# Ardumouse-LiION_rev3.net
KiCad netlist of a schematic drawn in EAGLE
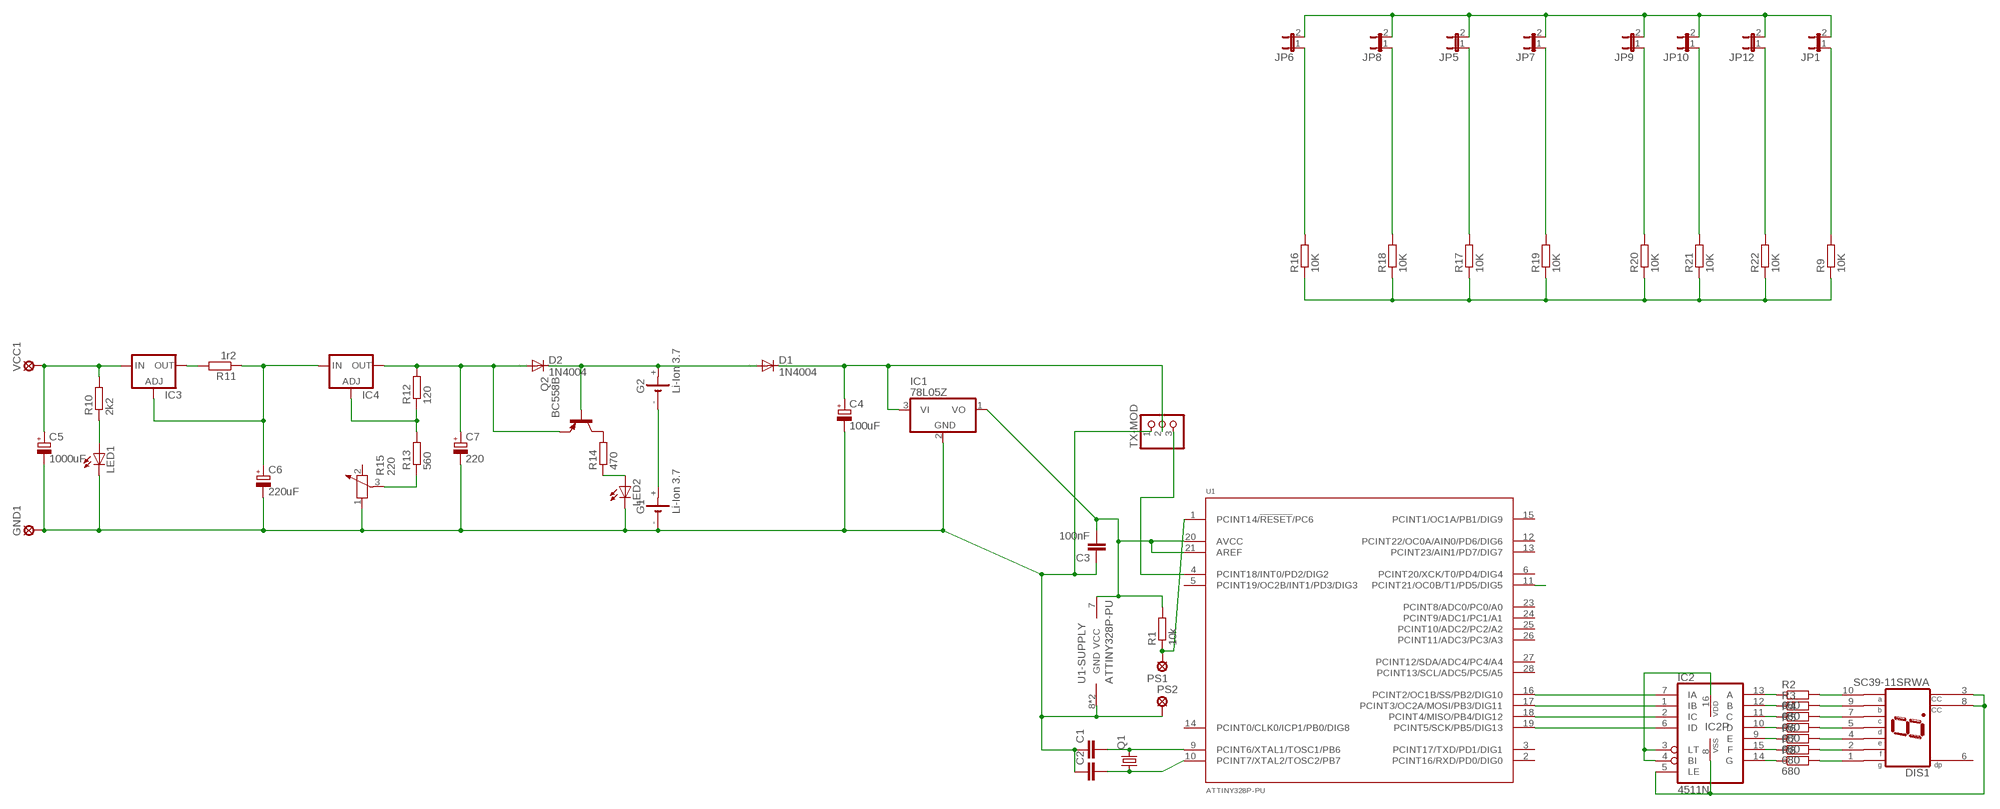
[diagram p0: schematic, sheet 1]

(export (version "E")
  (design (tool "Eeschema 10.0.6"))
  (components
    (comp (ref "C1")
      (value "C2,5-3")
      (footprint "eagle-import:C2.5-3")
      (libsource (lib "eagle-import") (part "C2,5-3"))
    )
    (comp (ref "C2")
      (value "C2,5-3")
      (footprint "eagle-import:C2.5-3")
      (libsource (lib "eagle-import") (part "C2,5-3"))
    )
    (comp (ref "C3")
      (value "100nF")
      (footprint "eagle-import:C2.5-3")
      (libsource (lib "eagle-import") (part "C2,5-3"))
    )
    (comp (ref "C4")
      (value "100uF")
      (footprint "eagle-import:E3,5-8")
      (libsource (lib "eagle-import") (part "resistor_CPOL-EUE3.5-8"))
    )
    (comp (ref "C5")
      (value "1000uF")
      (footprint "eagle-import:E3,5-8")
      (libsource (lib "eagle-import") (part "CPOL-EUE3.5-8"))
    )
    (comp (ref "C6")
      (value "220uF")
      (footprint "eagle-import:E3,5-8")
      (libsource (lib "eagle-import") (part "CPOL-EUE3.5-8"))
    )
    (comp (ref "C7")
      (value "220")
      (footprint "eagle-import:E3,5-8")
      (libsource (lib "eagle-import") (part "CPOL-EUE3.5-8"))
    )
    (comp (ref "D1")
      (value "1N4004")
      (footprint "eagle-import:DO41-10")
      (libsource (lib "eagle-import") (part "1N4004"))
    )
    (comp (ref "D2")
      (value "1N4004")
      (footprint "eagle-import:DO41-10")
      (libsource (lib "eagle-import") (part "1N4004"))
    )
    (comp (ref "DIS1")
      (value "SC39-11SRWA")
      (footprint "eagle-import:HDSP-E")
      (libsource (lib "eagle-import") (part "SC39-11SRWA"))
    )
    (comp (ref "G1")
      (value "Li-Ion 3.7")
      (footprint "eagle-import:SL-160AA_PR")
      (libsource (lib "eagle-import") (part "SL-160AA/PR"))
    )
    (comp (ref "G2")
      (value "Li-Ion 3.7")
      (footprint "eagle-import:SL-160AA_PR")
      (libsource (lib "eagle-import") (part "SL-160AA/PR"))
    )
    (comp (ref "GND1")
      (value "LSP13")
      (footprint "eagle-import:LSP13")
      (libsource (lib "eagle-import") (part "LSP13"))
    )
    (comp (ref "IC1")
      (value "78L05Z")
      (footprint "eagle-import:TO92")
      (libsource (lib "eagle-import") (part "78ZL05"))
    )
    (comp (ref "IC2")
      (value "4511N")
      (footprint "eagle-import:DIL16")
      (libsource (lib "eagle-import") (part "4511N"))
    )
    (comp (ref "IC3")
      (value "LM317TS")
      (footprint "eagle-import:317TS")
      (libsource (lib "eagle-import") (part "LM317TS"))
    )
    (comp (ref "IC4")
      (value "LM317TS")
      (footprint "eagle-import:317TS")
      (libsource (lib "eagle-import") (part "LM317TS"))
    )
    (comp (ref "JP1")
      (value "JP1E")
      (footprint "eagle-import:JP1")
      (libsource (lib "eagle-import") (part "JP1E"))
    )
    (comp (ref "JP5")
      (value "JP1E")
      (footprint "eagle-import:JP1")
      (libsource (lib "eagle-import") (part "JP1E"))
    )
    (comp (ref "JP6")
      (value "JP1E")
      (footprint "eagle-import:JP1")
      (libsource (lib "eagle-import") (part "JP1E"))
    )
    (comp (ref "JP7")
      (value "JP1E")
      (footprint "eagle-import:JP1")
      (libsource (lib "eagle-import") (part "JP1E"))
    )
    (comp (ref "JP8")
      (value "JP1E")
      (footprint "eagle-import:JP1")
      (libsource (lib "eagle-import") (part "JP1E"))
    )
    (comp (ref "JP9")
      (value "JP1E")
      (footprint "eagle-import:JP1")
      (libsource (lib "eagle-import") (part "JP1E"))
    )
    (comp (ref "JP10")
      (value "JP1E")
      (footprint "eagle-import:JP1")
      (libsource (lib "eagle-import") (part "JP1E"))
    )
    (comp (ref "JP12")
      (value "JP1E")
      (footprint "eagle-import:JP1")
      (libsource (lib "eagle-import") (part "JP1E"))
    )
    (comp (ref "LED1")
      (value "LED5MM")
      (footprint "eagle-import:LED5MM")
      (libsource (lib "eagle-import") (part "LED5MM"))
    )
    (comp (ref "LED2")
      (value "LED5MM")
      (footprint "eagle-import:LED5MM")
      (libsource (lib "eagle-import") (part "LED5MM"))
    )
    (comp (ref "PS1")
      (value "LSP10")
      (footprint "eagle-import:LSP10")
      (libsource (lib "eagle-import") (part "LSP10"))
    )
    (comp (ref "PS2")
      (value "LSP10")
      (footprint "eagle-import:LSP10")
      (libsource (lib "eagle-import") (part "LSP10"))
    )
    (comp (ref "Q1")
      (value "CRYSTALHC49S")
      (footprint "eagle-import:HC49_S")
      (libsource (lib "eagle-import") (part "CRYSTALHC49S"))
    )
    (comp (ref "Q2")
      (value "BC558B")
      (footprint "eagle-import:TO92-EBC")
      (libsource (lib "eagle-import") (part "BC558B"))
    )
    (comp (ref "R1")
      (value "10k")
      (footprint "eagle-import:0204_7")
      (libsource (lib "eagle-import") (part "resistor_R-EU_0204/7"))
    )
    (comp (ref "R2")
      (value "680")
      (footprint "eagle-import:0204_7")
      (libsource (lib "eagle-import") (part "resistor_R-EU_0204/7"))
    )
    (comp (ref "R3")
      (value "680")
      (footprint "eagle-import:0204_7")
      (libsource (lib "eagle-import") (part "resistor_R-EU_0204/7"))
    )
    (comp (ref "R4")
      (value "680")
      (footprint "eagle-import:0204_7")
      (libsource (lib "eagle-import") (part "resistor_R-EU_0204/7"))
    )
    (comp (ref "R5")
      (value "680")
      (footprint "eagle-import:0204_7")
      (libsource (lib "eagle-import") (part "resistor_R-EU_0204/7"))
    )
    (comp (ref "R6")
      (value "680")
      (footprint "eagle-import:0204_7")
      (libsource (lib "eagle-import") (part "resistor_R-EU_0204/7"))
    )
    (comp (ref "R7")
      (value "680")
      (footprint "eagle-import:0204_7")
      (libsource (lib "eagle-import") (part "resistor_R-EU_0204/7"))
    )
    (comp (ref "R8")
      (value "680")
      (footprint "eagle-import:0204_7")
      (libsource (lib "eagle-import") (part "resistor_R-EU_0204/7"))
    )
    (comp (ref "R9")
      (value "10K")
      (footprint "eagle-import:0204_7")
      (libsource (lib "eagle-import") (part "R-EU_0204/7"))
    )
    (comp (ref "R10")
      (value "2k2")
      (footprint "eagle-import:0207_7")
      (libsource (lib "eagle-import") (part "R-EU_0207/7"))
    )
    (comp (ref "R11")
      (value "1r2")
      (footprint "eagle-import:0207_7")
      (libsource (lib "eagle-import") (part "R-EU_0207/7"))
    )
    (comp (ref "R12")
      (value "120")
      (footprint "eagle-import:0207_7")
      (libsource (lib "eagle-import") (part "R-EU_0207/7"))
    )
    (comp (ref "R13")
      (value "560")
      (footprint "eagle-import:0207_7")
      (libsource (lib "eagle-import") (part "R-EU_0207/7"))
    )
    (comp (ref "R14")
      (value "470")
      (footprint "eagle-import:0207_7")
      (libsource (lib "eagle-import") (part "R-EU_0207/7"))
    )
    (comp (ref "R15")
      (value "220")
      (footprint "eagle-import:PT-10")
      (libsource (lib "eagle-import") (part "POTENTIOMETER_PT-10"))
    )
    (comp (ref "R16")
      (value "10K")
      (footprint "eagle-import:0204_7")
      (libsource (lib "eagle-import") (part "R-EU_0204/7"))
    )
    (comp (ref "R17")
      (value "10K")
      (footprint "eagle-import:0204_7")
      (libsource (lib "eagle-import") (part "R-EU_0204/7"))
    )
    (comp (ref "R18")
      (value "10K")
      (footprint "eagle-import:0204_7")
      (libsource (lib "eagle-import") (part "R-EU_0204/7"))
    )
    (comp (ref "R19")
      (value "10K")
      (footprint "eagle-import:0204_7")
      (libsource (lib "eagle-import") (part "R-EU_0204/7"))
    )
    (comp (ref "R20")
      (value "10K")
      (footprint "eagle-import:0204_7")
      (libsource (lib "eagle-import") (part "R-EU_0204/7"))
    )
    (comp (ref "R21")
      (value "10K")
      (footprint "eagle-import:0204_7")
      (libsource (lib "eagle-import") (part "R-EU_0204/7"))
    )
    (comp (ref "R22")
      (value "10K")
      (footprint "eagle-import:0204_7")
      (libsource (lib "eagle-import") (part "R-EU_0204/7"))
    )
    (comp (ref "TX-MOD")
      (value "PINHD-1X3")
      (footprint "eagle-import:1X03")
      (libsource (lib "eagle-import") (part "PINHD-1X3"))
    )
    (comp (ref "U1")
      (value "ATTINY328P-PU")
      (footprint "eagle-import:DIP-28")
      (fields (field (name "MANUFACTURER") "Atmel") (field (name "PART_NUMBER") "ATMEGA328P-PU"))
      (libsource (lib "eagle-import") (part "ATTINY8P-?PU32"))
    )
    (comp (ref "VCC1")
      (value "LSP13")
      (footprint "eagle-import:LSP13")
      (libsource (lib "eagle-import") (part "LSP13"))
    )
  )
  (nets
    (net (code "1") (name "Net-(D1-PadA)") (class "Default")
      (node (ref "D1") (pin "A") (pinfunction "A_A") (pintype "passive"))
      (node (ref "D2") (pin "C") (pinfunction "C_C") (pintype "passive"))
      (node (ref "G2") (pin "+") (pinfunction "+_+") (pintype "passive"))
      (node (ref "Q2") (pin "B") (pinfunction "B_B") (pintype "passive"))
    )
    (net (code "2") (name "Net-(DIS1-A)") (class "Default")
      (node (ref "DIS1") (pin "10") (pinfunction "A_10") (pintype "passive"))
      (node (ref "R2") (pin "2") (pinfunction "2_2") (pintype "passive"))
    )
    (net (code "3") (name "Net-(DIS1-B)") (class "Default")
      (node (ref "DIS1") (pin "9") (pinfunction "B_9") (pintype "passive"))
      (node (ref "R3") (pin "2") (pinfunction "2_2") (pintype "passive"))
    )
    (net (code "4") (name "Net-(DIS1-C)") (class "Default")
      (node (ref "DIS1") (pin "7") (pinfunction "C_7") (pintype "passive"))
      (node (ref "R4") (pin "2") (pinfunction "2_2") (pintype "passive"))
    )
    (net (code "5") (name "Net-(DIS1-D)") (class "Default")
      (node (ref "DIS1") (pin "5") (pinfunction "D_5") (pintype "passive"))
      (node (ref "R5") (pin "2") (pinfunction "2_2") (pintype "passive"))
    )
    (net (code "6") (name "Net-(DIS1-E)") (class "Default")
      (node (ref "DIS1") (pin "4") (pinfunction "E_4") (pintype "passive"))
      (node (ref "R6") (pin "2") (pinfunction "2_2") (pintype "passive"))
    )
    (net (code "7") (name "Net-(DIS1-F)") (class "Default")
      (node (ref "DIS1") (pin "2") (pinfunction "F_2") (pintype "passive"))
      (node (ref "R7") (pin "2") (pinfunction "2_2") (pintype "passive"))
    )
    (net (code "8") (name "Net-(DIS1-G)") (class "Default")
      (node (ref "DIS1") (pin "1") (pinfunction "G_1") (pintype "passive"))
      (node (ref "R8") (pin "2") (pinfunction "2_2") (pintype "passive"))
    )
    (net (code "9") (name "Net-(G1-Pad+)") (class "Default")
      (node (ref "G1") (pin "+") (pinfunction "+_+") (pintype "passive"))
      (node (ref "G2") (pin "-") (pinfunction "-_-") (pintype "passive"))
    )
    (net (code "10") (name "Net-(IC1-GND)") (class "Default")
      (node (ref "C1") (pin "1") (pinfunction "1_1") (pintype "passive"))
      (node (ref "C2") (pin "1") (pinfunction "1_1") (pintype "passive"))
      (node (ref "C3") (pin "1") (pinfunction "1_1") (pintype "passive"))
      (node (ref "C4") (pin "-") (pinfunction "-_-") (pintype "passive"))
      (node (ref "C5") (pin "-") (pinfunction "-_-") (pintype "passive"))
      (node (ref "C6") (pin "-") (pinfunction "-_-") (pintype "passive"))
      (node (ref "C7") (pin "-") (pinfunction "-_-") (pintype "passive"))
      (node (ref "G1") (pin "-") (pinfunction "-_-") (pintype "passive"))
      (node (ref "GND1") (pin "MP") (pinfunction "MP_MP") (pintype "passive"))
      (node (ref "IC1") (pin "2") (pinfunction "GND_2") (pintype "passive"))
      (node (ref "LED1") (pin "K") (pinfunction "C_K") (pintype "passive"))
      (node (ref "LED2") (pin "K") (pinfunction "C_K") (pintype "passive"))
      (node (ref "PS2") (pin "MP") (pinfunction "MP_MP") (pintype "passive"))
      (node (ref "R15") (pin "1") (pinfunction "1_1") (pintype "passive"))
      (node (ref "TX-MOD") (pin "1") (pinfunction "1_1") (pintype "passive"))
      (node (ref "U1") (pin "22") (pinfunction "GND_22") (pintype "power_in"))
      (node (ref "U1") (pin "8") (pinfunction "GND_8") (pintype "power_in"))
    )
    (net (code "11") (name "Net-(IC1-VI)") (class "Default")
      (node (ref "C4") (pin "+") (pinfunction "+_+") (pintype "passive"))
      (node (ref "D1") (pin "C") (pinfunction "C_C") (pintype "passive"))
      (node (ref "IC1") (pin "3") (pinfunction "VI_3") (pintype "input"))
      (node (ref "TX-MOD") (pin "2") (pinfunction "2_2") (pintype "passive"))
    )
    (net (code "12") (name "Net-(IC1-VO)") (class "Default")
      (node (ref "C3") (pin "2") (pinfunction "2_2") (pintype "passive"))
      (node (ref "IC1") (pin "1") (pinfunction "VO_1") (pintype "passive"))
      (node (ref "R1") (pin "2") (pinfunction "2_2") (pintype "passive"))
      (node (ref "U1") (pin "20") (pinfunction "AVCC_20") (pintype "bidirectional"))
      (node (ref "U1") (pin "21") (pinfunction "AREF_21") (pintype "bidirectional"))
      (node (ref "U1") (pin "7") (pinfunction "VCC_7") (pintype "power_in"))
    )
    (net (code "13") (name "Net-(IC2A-A)") (class "Default")
      (node (ref "IC2") (pin "13") (pinfunction "A_13") (pintype "output"))
      (node (ref "R2") (pin "1") (pinfunction "1_1") (pintype "passive"))
    )
    (net (code "14") (name "Net-(IC2A-B)") (class "Default")
      (node (ref "IC2") (pin "12") (pinfunction "B_12") (pintype "output"))
      (node (ref "R3") (pin "1") (pinfunction "1_1") (pintype "passive"))
    )
    (net (code "15") (name "Net-(IC2A-BI)") (class "Default")
      (node (ref "IC2") (pin "16") (pinfunction "VDD_16") (pintype "power_in"))
      (node (ref "IC2") (pin "3") (pinfunction "LT_3") (pintype "input"))
      (node (ref "IC2") (pin "4") (pinfunction "BI_4") (pintype "input"))
    )
    (net (code "16") (name "Net-(IC2A-C)") (class "Default")
      (node (ref "IC2") (pin "11") (pinfunction "C_11") (pintype "output"))
      (node (ref "R4") (pin "1") (pinfunction "1_1") (pintype "passive"))
    )
    (net (code "17") (name "Net-(IC2A-D)") (class "Default")
      (node (ref "IC2") (pin "10") (pinfunction "D_10") (pintype "output"))
      (node (ref "R5") (pin "1") (pinfunction "1_1") (pintype "passive"))
    )
    (net (code "18") (name "Net-(IC2A-E)") (class "Default")
      (node (ref "IC2") (pin "9") (pinfunction "E_9") (pintype "output"))
      (node (ref "R6") (pin "1") (pinfunction "1_1") (pintype "passive"))
    )
    (net (code "19") (name "Net-(IC2A-F)") (class "Default")
      (node (ref "IC2") (pin "15") (pinfunction "F_15") (pintype "output"))
      (node (ref "R7") (pin "1") (pinfunction "1_1") (pintype "passive"))
    )
    (net (code "20") (name "Net-(IC2A-G)") (class "Default")
      (node (ref "IC2") (pin "14") (pinfunction "G_14") (pintype "output"))
      (node (ref "R8") (pin "1") (pinfunction "1_1") (pintype "passive"))
    )
    (net (code "21") (name "Net-(IC2A-IA)") (class "Default")
      (node (ref "IC2") (pin "7") (pinfunction "IA_7") (pintype "input"))
      (node (ref "U1") (pin "16") (pinfunction "PCINT2/OC1B/SS/PB2/DIG10_16") (pintype "bidirectional"))
    )
    (net (code "22") (name "Net-(IC2A-IB)") (class "Default")
      (node (ref "IC2") (pin "1") (pinfunction "IB_1") (pintype "input"))
      (node (ref "U1") (pin "17") (pinfunction "PCINT3/OC2A/MOSI/PB3/DIG11_17") (pintype "bidirectional"))
    )
    (net (code "23") (name "Net-(IC2A-IC)") (class "Default")
      (node (ref "IC2") (pin "2") (pinfunction "IC_2") (pintype "input"))
      (node (ref "U1") (pin "18") (pinfunction "PCINT4/MISO/PB4/DIG12_18") (pintype "bidirectional"))
    )
    (net (code "24") (name "Net-(IC2A-ID)") (class "Default")
      (node (ref "IC2") (pin "6") (pinfunction "ID_6") (pintype "input"))
      (node (ref "U1") (pin "19") (pinfunction "PCINT5/SCK/PB5/DIG13_19") (pintype "bidirectional"))
    )
    (net (code "25") (name "Net-(IC2A-LE)") (class "Default")
      (node (ref "DIS1") (pin "3") (pinfunction "CC_3") (pintype "passive"))
      (node (ref "DIS1") (pin "8") (pinfunction "CC_8") (pintype "passive"))
      (node (ref "IC2") (pin "5") (pinfunction "LE_5") (pintype "input"))
      (node (ref "IC2") (pin "8") (pinfunction "VSS_8") (pintype "power_in"))
    )
    (net (code "26") (name "Net-(IC3-ADJ)") (class "Default")
      (node (ref "C6") (pin "+") (pinfunction "+_+") (pintype "passive"))
      (node (ref "IC3") (pin "1") (pinfunction "ADJ_1") (pintype "input"))
      (node (ref "IC4") (pin "3") (pinfunction "IN_3") (pintype "input"))
      (node (ref "R11") (pin "1") (pinfunction "1_1") (pintype "passive"))
    )
    (net (code "27") (name "Net-(IC3-IN)") (class "Default")
      (node (ref "C5") (pin "+") (pinfunction "+_+") (pintype "passive"))
      (node (ref "IC3") (pin "3") (pinfunction "IN_3") (pintype "input"))
      (node (ref "R10") (pin "2") (pinfunction "2_2") (pintype "passive"))
      (node (ref "VCC1") (pin "MP") (pinfunction "MP_MP") (pintype "passive"))
    )
    (net (code "28") (name "Net-(IC3-OUT)") (class "Default")
      (node (ref "IC3") (pin "2") (pinfunction "OUT_2") (pintype "passive"))
      (node (ref "R11") (pin "2") (pinfunction "2_2") (pintype "passive"))
    )
    (net (code "29") (name "Net-(IC4-ADJ)") (class "Default")
      (node (ref "IC4") (pin "1") (pinfunction "ADJ_1") (pintype "input"))
      (node (ref "R12") (pin "1") (pinfunction "1_1") (pintype "passive"))
      (node (ref "R13") (pin "2") (pinfunction "2_2") (pintype "passive"))
    )
    (net (code "30") (name "Net-(IC4-OUT)") (class "Default")
      (node (ref "C7") (pin "+") (pinfunction "+_+") (pintype "passive"))
      (node (ref "D2") (pin "A") (pinfunction "A_A") (pintype "passive"))
      (node (ref "IC4") (pin "2") (pinfunction "OUT_2") (pintype "passive"))
      (node (ref "Q2") (pin "E") (pinfunction "E_E") (pintype "passive"))
      (node (ref "R12") (pin "2") (pinfunction "2_2") (pintype "passive"))
    )
    (net (code "31") (name "Net-(JP1-Pad1)") (class "Default")
      (node (ref "JP1") (pin "1") (pinfunction "1_1") (pintype "passive"))
      (node (ref "R9") (pin "2") (pinfunction "2_2") (pintype "passive"))
    )
    (net (code "32") (name "Net-(JP1-Pad2)") (class "Default")
      (node (ref "JP1") (pin "2") (pinfunction "2_2") (pintype "passive"))
      (node (ref "JP10") (pin "2") (pinfunction "2_2") (pintype "passive"))
      (node (ref "JP12") (pin "2") (pinfunction "2_2") (pintype "passive"))
      (node (ref "JP5") (pin "2") (pinfunction "2_2") (pintype "passive"))
      (node (ref "JP6") (pin "2") (pinfunction "2_2") (pintype "passive"))
      (node (ref "JP7") (pin "2") (pinfunction "2_2") (pintype "passive"))
      (node (ref "JP8") (pin "2") (pinfunction "2_2") (pintype "passive"))
      (node (ref "JP9") (pin "2") (pinfunction "2_2") (pintype "passive"))
    )
    (net (code "33") (name "Net-(JP5-Pad1)") (class "Default")
      (node (ref "JP5") (pin "1") (pinfunction "1_1") (pintype "passive"))
      (node (ref "R17") (pin "2") (pinfunction "2_2") (pintype "passive"))
    )
    (net (code "34") (name "Net-(JP6-Pad1)") (class "Default")
      (node (ref "JP6") (pin "1") (pinfunction "1_1") (pintype "passive"))
      (node (ref "R16") (pin "2") (pinfunction "2_2") (pintype "passive"))
    )
    (net (code "35") (name "Net-(JP7-Pad1)") (class "Default")
      (node (ref "JP7") (pin "1") (pinfunction "1_1") (pintype "passive"))
      (node (ref "R19") (pin "2") (pinfunction "2_2") (pintype "passive"))
    )
    (net (code "36") (name "Net-(JP8-Pad1)") (class "Default")
      (node (ref "JP8") (pin "1") (pinfunction "1_1") (pintype "passive"))
      (node (ref "R18") (pin "2") (pinfunction "2_2") (pintype "passive"))
    )
    (net (code "37") (name "Net-(JP9-Pad1)") (class "Default")
      (node (ref "JP9") (pin "1") (pinfunction "1_1") (pintype "passive"))
      (node (ref "R20") (pin "2") (pinfunction "2_2") (pintype "passive"))
    )
    (net (code "38") (name "Net-(JP10-Pad1)") (class "Default")
      (node (ref "JP10") (pin "1") (pinfunction "1_1") (pintype "passive"))
      (node (ref "R21") (pin "2") (pinfunction "2_2") (pintype "passive"))
    )
    (net (code "39") (name "Net-(JP12-Pad1)") (class "Default")
      (node (ref "JP12") (pin "1") (pinfunction "1_1") (pintype "passive"))
      (node (ref "R22") (pin "2") (pinfunction "2_2") (pintype "passive"))
    )
    (net (code "40") (name "Net-(LED1-PadA)") (class "Default")
      (node (ref "LED1") (pin "A") (pinfunction "A_A") (pintype "passive"))
      (node (ref "R10") (pin "1") (pinfunction "1_1") (pintype "passive"))
    )
    (net (code "41") (name "Net-(LED2-PadA)") (class "Default")
      (node (ref "LED2") (pin "A") (pinfunction "A_A") (pintype "passive"))
      (node (ref "R14") (pin "1") (pinfunction "1_1") (pintype "passive"))
    )
    (net (code "42") (name "Net-(Q2-PadC)") (class "Default")
      (node (ref "Q2") (pin "C") (pinfunction "C_C") (pintype "passive"))
      (node (ref "R14") (pin "2") (pinfunction "2_2") (pintype "passive"))
    )
    (net (code "43") (name "Net-(R13-Pad1)") (class "Default")
      (node (ref "R13") (pin "1") (pinfunction "1_1") (pintype "passive"))
      (node (ref "R15") (pin "3") (pinfunction "3_3") (pintype "passive"))
    )
    (net (code "44") (name "Net-(R16-Pad1)") (class "Default")
      (node (ref "R16") (pin "1") (pinfunction "1_1") (pintype "passive"))
      (node (ref "R17") (pin "1") (pinfunction "1_1") (pintype "passive"))
      (node (ref "R18") (pin "1") (pinfunction "1_1") (pintype "passive"))
      (node (ref "R19") (pin "1") (pinfunction "1_1") (pintype "passive"))
      (node (ref "R20") (pin "1") (pinfunction "1_1") (pintype "passive"))
      (node (ref "R21") (pin "1") (pinfunction "1_1") (pintype "passive"))
      (node (ref "R22") (pin "1") (pinfunction "1_1") (pintype "passive"))
      (node (ref "R9") (pin "1") (pinfunction "1_1") (pintype "passive"))
    )
    (net (code "45") (name "Net-(U1B-PCINT6{slash}XTAL1{slash}TOSC1{slash}PB6)") (class "Default")
      (node (ref "C1") (pin "2") (pinfunction "2_2") (pintype "passive"))
      (node (ref "Q1") (pin "2") (pinfunction "2_2") (pintype "passive"))
      (node (ref "U1") (pin "9") (pinfunction "PCINT6/XTAL1/TOSC1/PB6_9") (pintype "bidirectional"))
    )
    (net (code "46") (name "Net-(U1B-PCINT7{slash}XTAL2{slash}TOSC2{slash}PB7)") (class "Default")
      (node (ref "C2") (pin "2") (pinfunction "2_2") (pintype "passive"))
      (node (ref "Q1") (pin "1") (pinfunction "1_1") (pintype "passive"))
      (node (ref "U1") (pin "10") (pinfunction "PCINT7/XTAL2/TOSC2/PB7_10") (pintype "bidirectional"))
    )
    (net (code "47") (name "Net-(U1B-PCINT14{slash}~{RESET}{slash}PC6)") (class "Default")
      (node (ref "PS1") (pin "MP") (pinfunction "MP_MP") (pintype "passive"))
      (node (ref "R1") (pin "1") (pinfunction "1_1") (pintype "passive"))
      (node (ref "U1") (pin "1") (pinfunction "PCINT14/~{RESET}/PC6_1") (pintype "bidirectional"))
    )
    (net (code "48") (name "Net-(U1B-PCINT18{slash}INT0{slash}PD2{slash}DIG2)") (class "Default")
      (node (ref "TX-MOD") (pin "3") (pinfunction "3_3") (pintype "passive"))
      (node (ref "U1") (pin "4") (pinfunction "PCINT18/INT0/PD2/DIG2_4") (pintype "bidirectional"))
    )
    (net (code "49") (name "unconnected-(DIS1-DP-Pad6)") (class "Default")
      (node (ref "DIS1") (pin "6") (pinfunction "DP_6") (pintype "passive"))
    )
    (net (code "50") (name "unconnected-(R15-Pad2)") (class "Default")
      (node (ref "R15") (pin "2") (pinfunction "2_2") (pintype "passive"))
    )
    (net (code "51") (name "unconnected-(U1B-PCINT0{slash}CLK0{slash}ICP1{slash}PB0{slash}DIG8-Pad14)") (class "Default")
      (node (ref "U1") (pin "14") (pinfunction "PCINT0/CLK0/ICP1/PB0/DIG8_14") (pintype "bidirectional"))
    )
    (net (code "52") (name "unconnected-(U1B-PCINT1{slash}OC1A{slash}PB1{slash}DIG9-Pad15)") (class "Default")
      (node (ref "U1") (pin "15") (pinfunction "PCINT1/OC1A/PB1/DIG9_15") (pintype "bidirectional"))
    )
    (net (code "53") (name "unconnected-(U1B-PCINT8{slash}ADC0{slash}PC0{slash}A0-Pad23)") (class "Default")
      (node (ref "U1") (pin "23") (pinfunction "PCINT8/ADC0/PC0/A0_23") (pintype "bidirectional"))
    )
    (net (code "54") (name "unconnected-(U1B-PCINT9{slash}ADC1{slash}PC1{slash}A1-Pad24)") (class "Default")
      (node (ref "U1") (pin "24") (pinfunction "PCINT9/ADC1/PC1/A1_24") (pintype "bidirectional"))
    )
    (net (code "55") (name "unconnected-(U1B-PCINT10{slash}ADC2{slash}PC2{slash}A2-Pad25)") (class "Default")
      (node (ref "U1") (pin "25") (pinfunction "PCINT10/ADC2/PC2/A2_25") (pintype "bidirectional"))
    )
    (net (code "56") (name "unconnected-(U1B-PCINT11{slash}ADC3{slash}PC3{slash}A3-Pad26)") (class "Default")
      (node (ref "U1") (pin "26") (pinfunction "PCINT11/ADC3/PC3/A3_26") (pintype "bidirectional"))
    )
    (net (code "57") (name "unconnected-(U1B-PCINT12{slash}SDA{slash}ADC4{slash}PC4{slash}A4-Pad27)") (class "Default")
      (node (ref "U1") (pin "27") (pinfunction "PCINT12/SDA/ADC4/PC4/A4_27") (pintype "bidirectional"))
    )
    (net (code "58") (name "unconnected-(U1B-PCINT13{slash}SCL{slash}ADC5{slash}PC5{slash}A5-Pad28)") (class "Default")
      (node (ref "U1") (pin "28") (pinfunction "PCINT13/SCL/ADC5/PC5/A5_28") (pintype "bidirectional"))
    )
    (net (code "59") (name "unconnected-(U1B-PCINT16{slash}RXD{slash}PD0{slash}DIG0-Pad2)") (class "Default")
      (node (ref "U1") (pin "2") (pinfunction "PCINT16/RXD/PD0/DIG0_2") (pintype "bidirectional"))
    )
    (net (code "60") (name "unconnected-(U1B-PCINT17{slash}TXD{slash}PD1{slash}DIG1-Pad3)") (class "Default")
      (node (ref "U1") (pin "3") (pinfunction "PCINT17/TXD/PD1/DIG1_3") (pintype "bidirectional"))
    )
    (net (code "61") (name "unconnected-(U1B-PCINT19{slash}OC2B{slash}INT1{slash}PD3{slash}DIG3-Pad5)") (class "Default")
      (node (ref "U1") (pin "5") (pinfunction "PCINT19/OC2B/INT1/PD3/DIG3_5") (pintype "bidirectional"))
    )
    (net (code "62") (name "unconnected-(U1B-PCINT20{slash}XCK{slash}T0{slash}PD4{slash}DIG4-Pad6)") (class "Default")
      (node (ref "U1") (pin "6") (pinfunction "PCINT20/XCK/T0/PD4/DIG4_6") (pintype "bidirectional"))
    )
    (net (code "63") (name "unconnected-(U1B-PCINT21{slash}OC0B{slash}T1{slash}PD5{slash}DIG5-Pad11)") (class "Default")
      (node (ref "U1") (pin "11") (pinfunction "PCINT21/OC0B/T1/PD5/DIG5_11") (pintype "bidirectional"))
    )
    (net (code "64") (name "unconnected-(U1B-PCINT22{slash}OC0A{slash}AIN0{slash}PD6{slash}DIG6-Pad12)") (class "Default")
      (node (ref "U1") (pin "12") (pinfunction "PCINT22/OC0A/AIN0/PD6/DIG6_12") (pintype "bidirectional"))
    )
    (net (code "65") (name "unconnected-(U1B-PCINT23{slash}AIN1{slash}PD7{slash}DIG7-Pad13)") (class "Default")
      (node (ref "U1") (pin "13") (pinfunction "PCINT23/AIN1/PD7/DIG7_13") (pintype "bidirectional"))
    )
  )
)
